# mux_side_A.net
KiCad netlist of a schematic drawn in Altium Designer
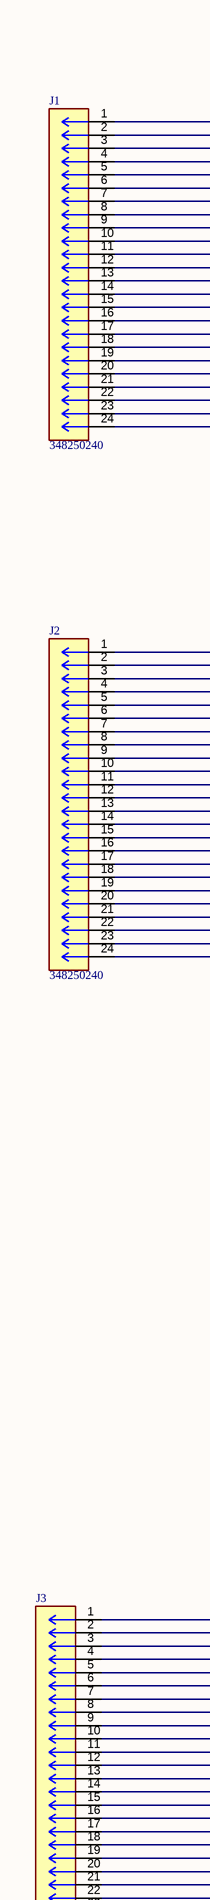
[diagram p0: mux side A (1-4).SchDoc, top left]
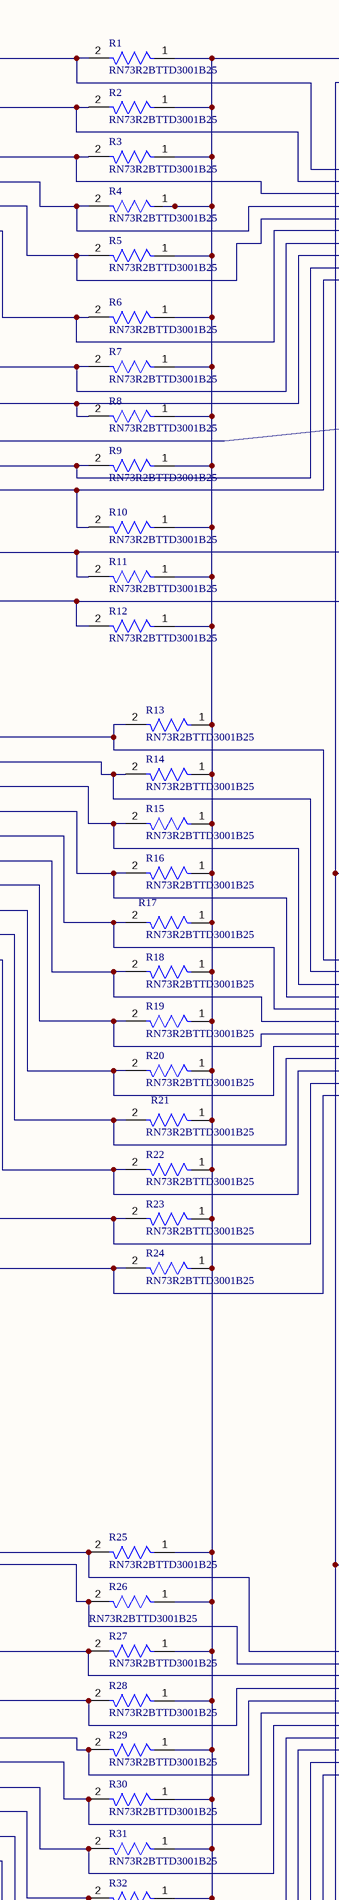
[diagram p1: mux side A (1-4).SchDoc, top middle]
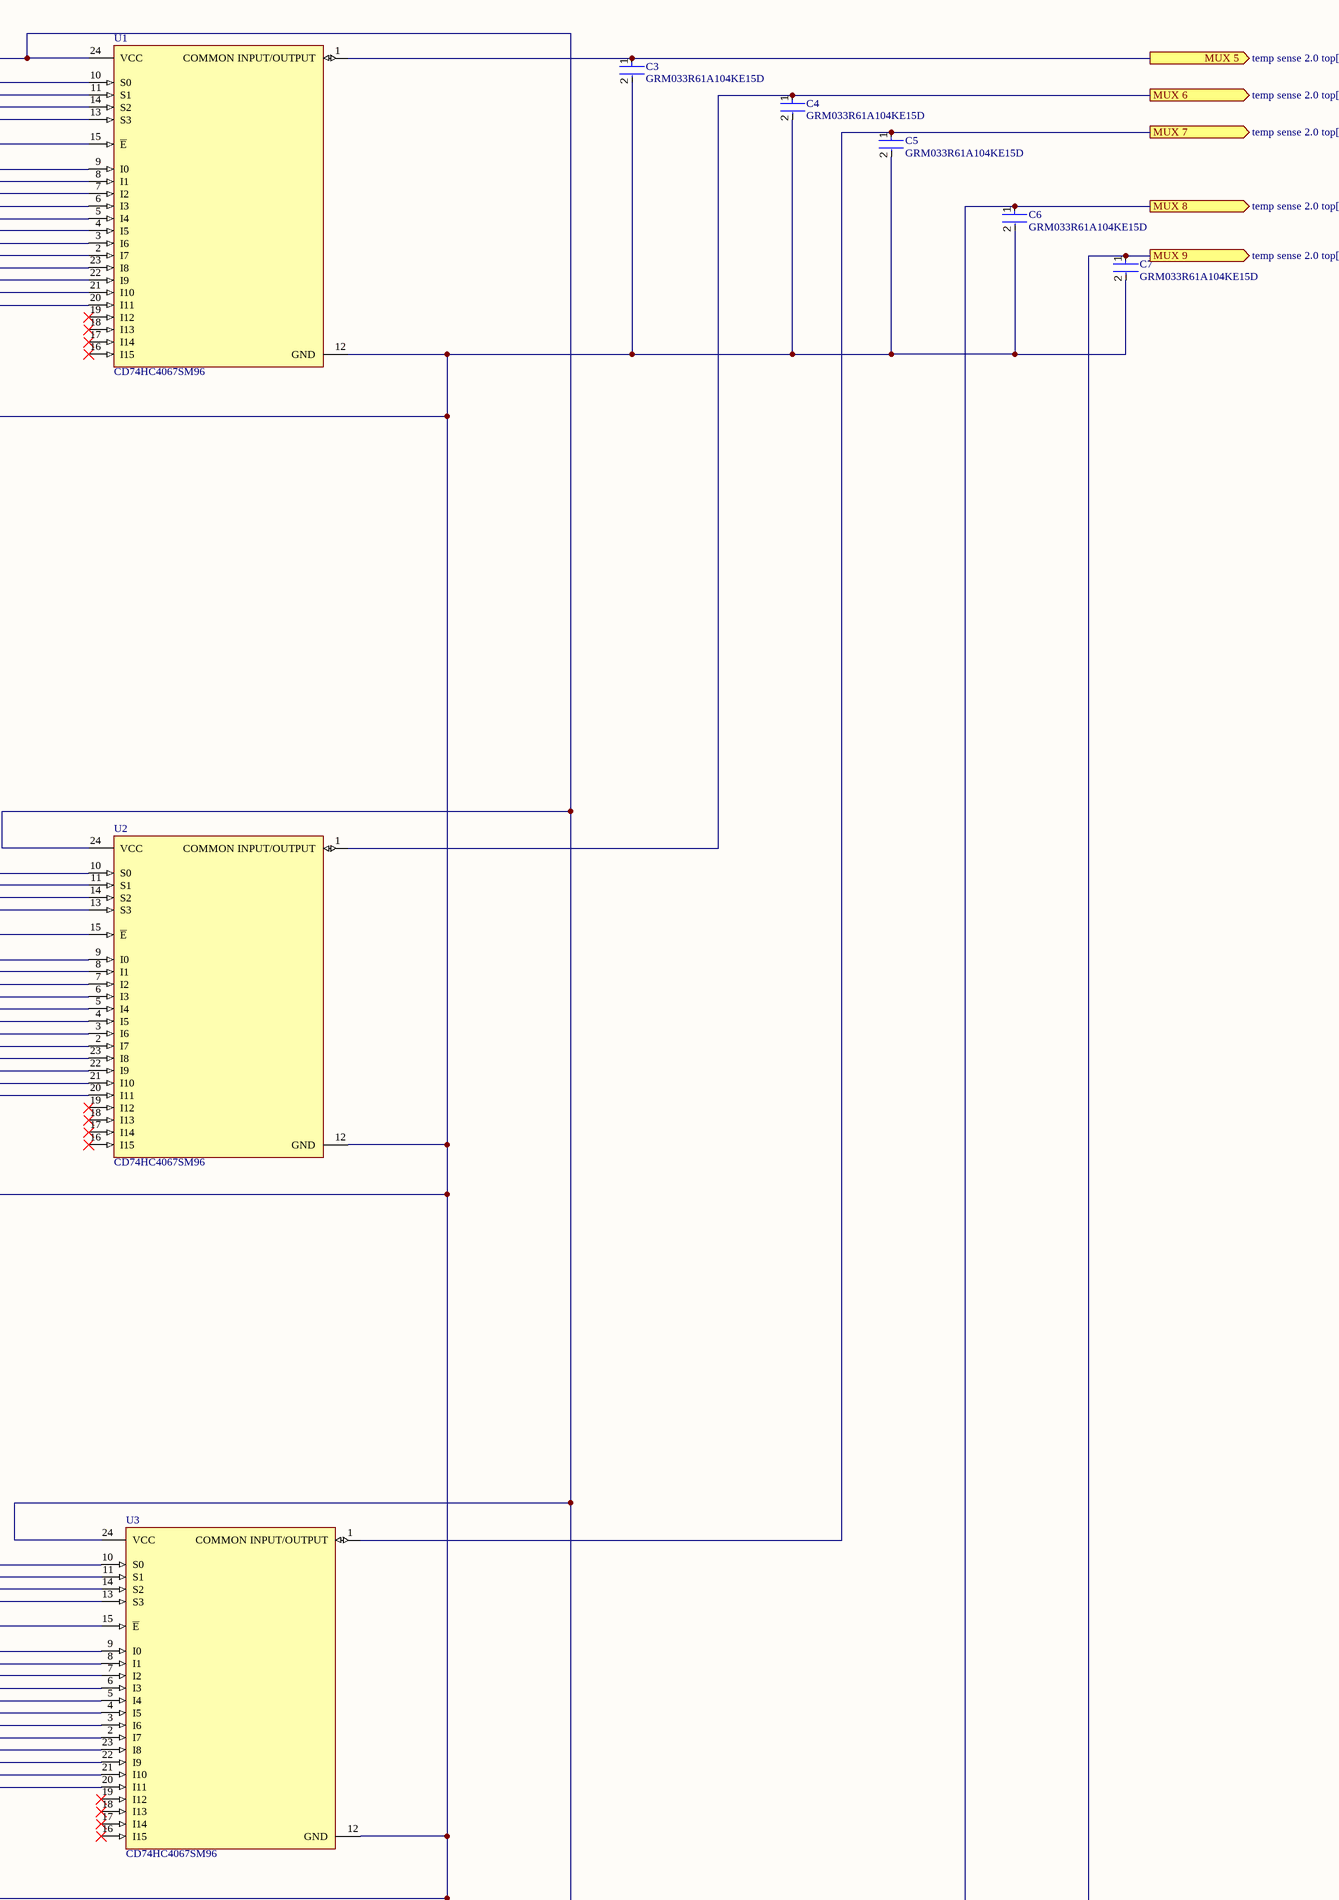
[diagram p2: mux side A (1-4).SchDoc, top right]
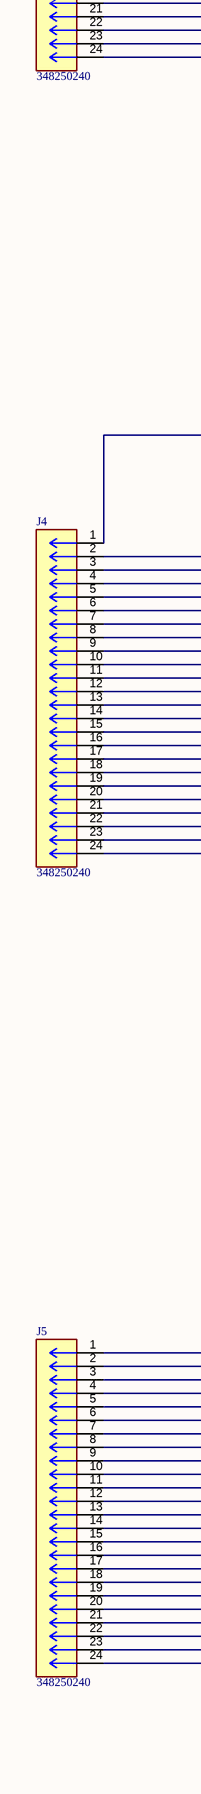
[diagram p3: mux side A (1-4).SchDoc, bottom left]
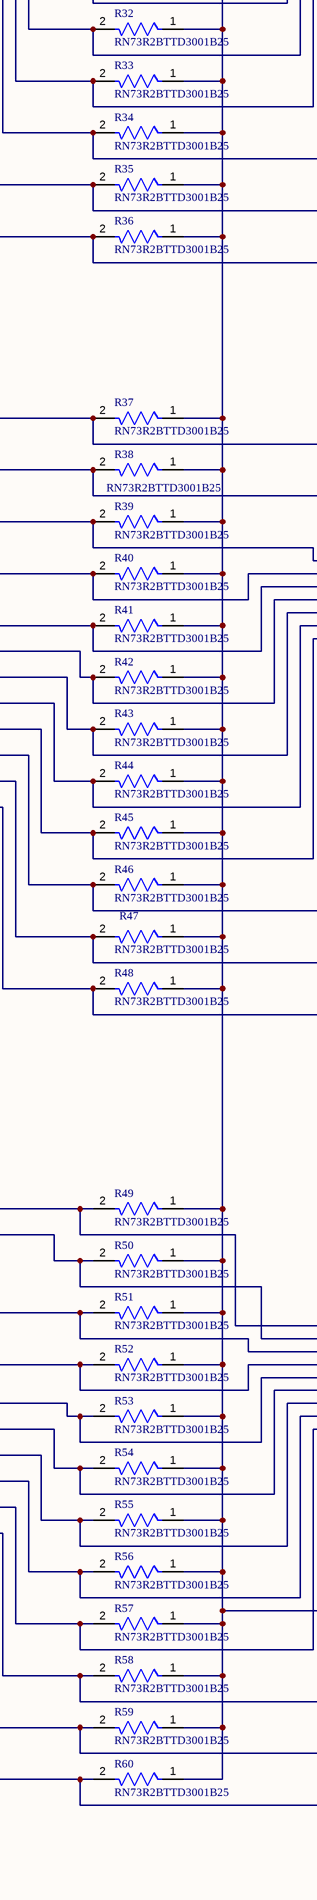
[diagram p4: mux side A (1-4).SchDoc, bottom middle]
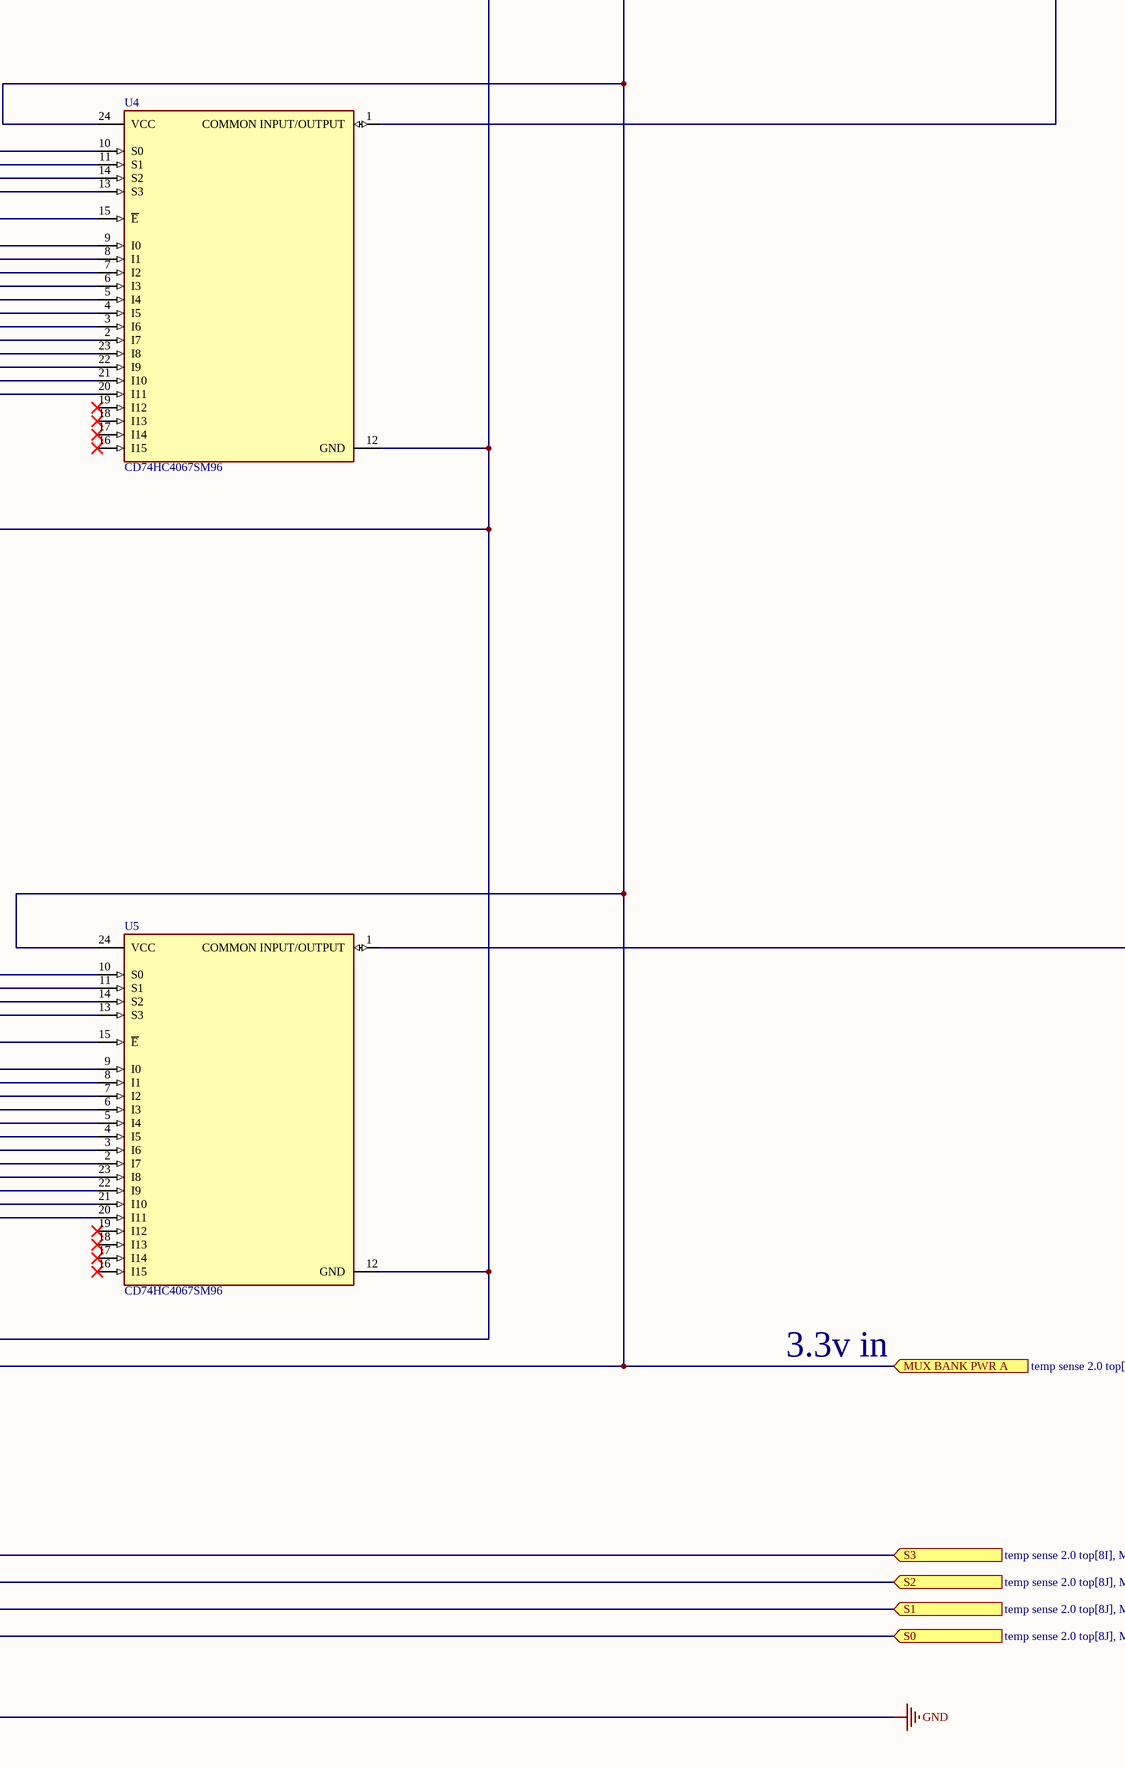
[diagram p5: mux side A (1-4).SchDoc, bottom right]

(export (version "E")
  (design (tool "Eeschema 10.0.6"))
  (components
    (comp (ref "C3")
      (value "GRM033R61A104KE15D")
      (footprint "FP-GRM033-0_03-IPC_C")
      (description "Chip Multilayer Ceramic Capacitors for General Purpose, 0201, 0.10uF, X5R, 15%, 10%, 10V")
      (fields (field (name "TOLERANCE") "10%") (field (name "VOLTAGE") "10V"))
      (libsource (lib "Altium Content Vault") (part "b4654b650e69147ec39a6b967a45e02"))
    )
    (comp (ref "C4")
      (value "GRM033R61A104KE15D")
      (footprint "FP-GRM033-0_03-IPC_C")
      (description "Chip Multilayer Ceramic Capacitors for General Purpose, 0201, 0.10uF, X5R, 15%, 10%, 10V")
      (fields (field (name "TOLERANCE") "10%") (field (name "VOLTAGE") "10V"))
      (libsource (lib "Altium Content Vault") (part "b4654b650e69147ec39a6b967a45e02"))
    )
    (comp (ref "C5")
      (value "GRM033R61A104KE15D")
      (footprint "FP-GRM033-0_03-IPC_C")
      (description "Chip Multilayer Ceramic Capacitors for General Purpose, 0201, 0.10uF, X5R, 15%, 10%, 10V")
      (fields (field (name "TOLERANCE") "10%") (field (name "VOLTAGE") "10V"))
      (libsource (lib "Altium Content Vault") (part "b4654b650e69147ec39a6b967a45e02"))
    )
    (comp (ref "C6")
      (value "GRM033R61A104KE15D")
      (footprint "FP-GRM033-0_03-IPC_C")
      (description "Chip Multilayer Ceramic Capacitors for General Purpose, 0201, 0.10uF, X5R, 15%, 10%, 10V")
      (fields (field (name "TOLERANCE") "10%") (field (name "VOLTAGE") "10V"))
      (libsource (lib "Altium Content Vault") (part "b4654b650e69147ec39a6b967a45e02"))
    )
    (comp (ref "C7")
      (value "GRM033R61A104KE15D")
      (footprint "FP-GRM033-0_03-IPC_C")
      (description "Chip Multilayer Ceramic Capacitors for General Purpose, 0201, 0.10uF, X5R, 15%, 10%, 10V")
      (fields (field (name "TOLERANCE") "10%") (field (name "VOLTAGE") "10V"))
      (libsource (lib "Altium Content Vault") (part "b4654b650e69147ec39a6b967a45e02"))
    )
    (comp (ref "J1")
      (value "348250240")
      (footprint "CONN_SD-34825-001_24_MOL")
      (libsource (lib "348250240") (part "348250240"))
    )
    (comp (ref "J2")
      (value "348250240")
      (footprint "CONN_SD-34825-001_24_MOL")
      (libsource (lib "348250240") (part "348250240"))
    )
    (comp (ref "J3")
      (value "348250240")
      (footprint "CONN_SD-34825-001_24_MOL")
      (libsource (lib "348250240") (part "348250240"))
    )
    (comp (ref "J4")
      (value "348250240")
      (footprint "CONN_SD-34825-001_24_MOL")
      (libsource (lib "348250240") (part "348250240"))
    )
    (comp (ref "J5")
      (value "348250240")
      (footprint "CONN_SD-34825-001_24_MOL")
      (libsource (lib "348250240") (part "348250240"))
    )
    (comp (ref "R1")
      (value "RN73R2BTTD3001B25")
      (footprint "FP-RN73R2B-IPC_A")
      (description "3kΩ ±0.1% 0.25W, 1/4W Chip Resistor 1206 (3216 Metric) Moisture Resistant Thin Film")
      (libsource (lib "Altium Content Vault") (part "1029c3af85768c4190bb7ad29bc67b5"))
    )
    (comp (ref "R2")
      (value "RN73R2BTTD3001B25")
      (footprint "FP-RN73R2B-IPC_A")
      (description "3kΩ ±0.1% 0.25W, 1/4W Chip Resistor 1206 (3216 Metric) Moisture Resistant Thin Film")
      (libsource (lib "Altium Content Vault") (part "1029c3af85768c4190bb7ad29bc67b5"))
    )
    (comp (ref "R3")
      (value "RN73R2BTTD3001B25")
      (footprint "FP-RN73R2B-IPC_A")
      (description "3kΩ ±0.1% 0.25W, 1/4W Chip Resistor 1206 (3216 Metric) Moisture Resistant Thin Film")
      (libsource (lib "Altium Content Vault") (part "1029c3af85768c4190bb7ad29bc67b5"))
    )
    (comp (ref "R4")
      (value "RN73R2BTTD3001B25")
      (footprint "FP-RN73R2B-IPC_A")
      (description "3kΩ ±0.1% 0.25W, 1/4W Chip Resistor 1206 (3216 Metric) Moisture Resistant Thin Film")
      (libsource (lib "Altium Content Vault") (part "1029c3af85768c4190bb7ad29bc67b5"))
    )
    (comp (ref "R5")
      (value "RN73R2BTTD3001B25")
      (footprint "FP-RN73R2B-IPC_A")
      (description "3kΩ ±0.1% 0.25W, 1/4W Chip Resistor 1206 (3216 Metric) Moisture Resistant Thin Film")
      (libsource (lib "Altium Content Vault") (part "1029c3af85768c4190bb7ad29bc67b5"))
    )
    (comp (ref "R6")
      (value "RN73R2BTTD3001B25")
      (footprint "FP-RN73R2B-IPC_A")
      (description "3kΩ ±0.1% 0.25W, 1/4W Chip Resistor 1206 (3216 Metric) Moisture Resistant Thin Film")
      (libsource (lib "Altium Content Vault") (part "1029c3af85768c4190bb7ad29bc67b5"))
    )
    (comp (ref "R7")
      (value "RN73R2BTTD3001B25")
      (footprint "FP-RN73R2B-IPC_A")
      (description "3kΩ ±0.1% 0.25W, 1/4W Chip Resistor 1206 (3216 Metric) Moisture Resistant Thin Film")
      (libsource (lib "Altium Content Vault") (part "1029c3af85768c4190bb7ad29bc67b5"))
    )
    (comp (ref "R8")
      (value "RN73R2BTTD3001B25")
      (footprint "FP-RN73R2B-IPC_A")
      (description "3kΩ ±0.1% 0.25W, 1/4W Chip Resistor 1206 (3216 Metric) Moisture Resistant Thin Film")
      (libsource (lib "Altium Content Vault") (part "1029c3af85768c4190bb7ad29bc67b5"))
    )
    (comp (ref "R9")
      (value "RN73R2BTTD3001B25")
      (footprint "FP-RN73R2B-IPC_A")
      (description "3kΩ ±0.1% 0.25W, 1/4W Chip Resistor 1206 (3216 Metric) Moisture Resistant Thin Film")
      (libsource (lib "Altium Content Vault") (part "1029c3af85768c4190bb7ad29bc67b5"))
    )
    (comp (ref "R10")
      (value "RN73R2BTTD3001B25")
      (footprint "FP-RN73R2B-IPC_A")
      (description "3kΩ ±0.1% 0.25W, 1/4W Chip Resistor 1206 (3216 Metric) Moisture Resistant Thin Film")
      (libsource (lib "Altium Content Vault") (part "1029c3af85768c4190bb7ad29bc67b5"))
    )
    (comp (ref "R11")
      (value "RN73R2BTTD3001B25")
      (footprint "FP-RN73R2B-IPC_A")
      (description "3kΩ ±0.1% 0.25W, 1/4W Chip Resistor 1206 (3216 Metric) Moisture Resistant Thin Film")
      (libsource (lib "Altium Content Vault") (part "1029c3af85768c4190bb7ad29bc67b5"))
    )
    (comp (ref "R12")
      (value "RN73R2BTTD3001B25")
      (footprint "FP-RN73R2B-IPC_A")
      (description "3kΩ ±0.1% 0.25W, 1/4W Chip Resistor 1206 (3216 Metric) Moisture Resistant Thin Film")
      (libsource (lib "Altium Content Vault") (part "1029c3af85768c4190bb7ad29bc67b5"))
    )
    (comp (ref "R13")
      (value "RN73R2BTTD3001B25")
      (footprint "FP-RN73R2B-IPC_A")
      (description "3kΩ ±0.1% 0.25W, 1/4W Chip Resistor 1206 (3216 Metric) Moisture Resistant Thin Film")
      (libsource (lib "Altium Content Vault") (part "1029c3af85768c4190bb7ad29bc67b5"))
    )
    (comp (ref "R14")
      (value "RN73R2BTTD3001B25")
      (footprint "FP-RN73R2B-IPC_A")
      (description "3kΩ ±0.1% 0.25W, 1/4W Chip Resistor 1206 (3216 Metric) Moisture Resistant Thin Film")
      (libsource (lib "Altium Content Vault") (part "1029c3af85768c4190bb7ad29bc67b5"))
    )
    (comp (ref "R15")
      (value "RN73R2BTTD3001B25")
      (footprint "FP-RN73R2B-IPC_A")
      (description "3kΩ ±0.1% 0.25W, 1/4W Chip Resistor 1206 (3216 Metric) Moisture Resistant Thin Film")
      (libsource (lib "Altium Content Vault") (part "1029c3af85768c4190bb7ad29bc67b5"))
    )
    (comp (ref "R16")
      (value "RN73R2BTTD3001B25")
      (footprint "FP-RN73R2B-IPC_A")
      (description "3kΩ ±0.1% 0.25W, 1/4W Chip Resistor 1206 (3216 Metric) Moisture Resistant Thin Film")
      (libsource (lib "Altium Content Vault") (part "1029c3af85768c4190bb7ad29bc67b5"))
    )
    (comp (ref "R17")
      (value "RN73R2BTTD3001B25")
      (footprint "FP-RN73R2B-IPC_A")
      (description "3kΩ ±0.1% 0.25W, 1/4W Chip Resistor 1206 (3216 Metric) Moisture Resistant Thin Film")
      (libsource (lib "Altium Content Vault") (part "1029c3af85768c4190bb7ad29bc67b5"))
    )
    (comp (ref "R18")
      (value "RN73R2BTTD3001B25")
      (footprint "FP-RN73R2B-IPC_A")
      (description "3kΩ ±0.1% 0.25W, 1/4W Chip Resistor 1206 (3216 Metric) Moisture Resistant Thin Film")
      (libsource (lib "Altium Content Vault") (part "1029c3af85768c4190bb7ad29bc67b5"))
    )
    (comp (ref "R19")
      (value "RN73R2BTTD3001B25")
      (footprint "FP-RN73R2B-IPC_A")
      (description "3kΩ ±0.1% 0.25W, 1/4W Chip Resistor 1206 (3216 Metric) Moisture Resistant Thin Film")
      (libsource (lib "Altium Content Vault") (part "1029c3af85768c4190bb7ad29bc67b5"))
    )
    (comp (ref "R20")
      (value "RN73R2BTTD3001B25")
      (footprint "FP-RN73R2B-IPC_A")
      (description "3kΩ ±0.1% 0.25W, 1/4W Chip Resistor 1206 (3216 Metric) Moisture Resistant Thin Film")
      (libsource (lib "Altium Content Vault") (part "1029c3af85768c4190bb7ad29bc67b5"))
    )
    (comp (ref "R21")
      (value "RN73R2BTTD3001B25")
      (footprint "FP-RN73R2B-IPC_A")
      (description "3kΩ ±0.1% 0.25W, 1/4W Chip Resistor 1206 (3216 Metric) Moisture Resistant Thin Film")
      (libsource (lib "Altium Content Vault") (part "1029c3af85768c4190bb7ad29bc67b5"))
    )
    (comp (ref "R22")
      (value "RN73R2BTTD3001B25")
      (footprint "FP-RN73R2B-IPC_A")
      (description "3kΩ ±0.1% 0.25W, 1/4W Chip Resistor 1206 (3216 Metric) Moisture Resistant Thin Film")
      (libsource (lib "Altium Content Vault") (part "1029c3af85768c4190bb7ad29bc67b5"))
    )
    (comp (ref "R23")
      (value "RN73R2BTTD3001B25")
      (footprint "FP-RN73R2B-IPC_A")
      (description "3kΩ ±0.1% 0.25W, 1/4W Chip Resistor 1206 (3216 Metric) Moisture Resistant Thin Film")
      (libsource (lib "Altium Content Vault") (part "1029c3af85768c4190bb7ad29bc67b5"))
    )
    (comp (ref "R24")
      (value "RN73R2BTTD3001B25")
      (footprint "FP-RN73R2B-IPC_A")
      (description "3kΩ ±0.1% 0.25W, 1/4W Chip Resistor 1206 (3216 Metric) Moisture Resistant Thin Film")
      (libsource (lib "Altium Content Vault") (part "1029c3af85768c4190bb7ad29bc67b5"))
    )
    (comp (ref "R25")
      (value "RN73R2BTTD3001B25")
      (footprint "FP-RN73R2B-IPC_A")
      (description "3kΩ ±0.1% 0.25W, 1/4W Chip Resistor 1206 (3216 Metric) Moisture Resistant Thin Film")
      (libsource (lib "Altium Content Vault") (part "1029c3af85768c4190bb7ad29bc67b5"))
    )
    (comp (ref "R26")
      (value "RN73R2BTTD3001B25")
      (footprint "FP-RN73R2B-IPC_A")
      (description "3kΩ ±0.1% 0.25W, 1/4W Chip Resistor 1206 (3216 Metric) Moisture Resistant Thin Film")
      (libsource (lib "Altium Content Vault") (part "1029c3af85768c4190bb7ad29bc67b5"))
    )
    (comp (ref "R27")
      (value "RN73R2BTTD3001B25")
      (footprint "FP-RN73R2B-IPC_A")
      (description "3kΩ ±0.1% 0.25W, 1/4W Chip Resistor 1206 (3216 Metric) Moisture Resistant Thin Film")
      (libsource (lib "Altium Content Vault") (part "1029c3af85768c4190bb7ad29bc67b5"))
    )
    (comp (ref "R28")
      (value "RN73R2BTTD3001B25")
      (footprint "FP-RN73R2B-IPC_A")
      (description "3kΩ ±0.1% 0.25W, 1/4W Chip Resistor 1206 (3216 Metric) Moisture Resistant Thin Film")
      (libsource (lib "Altium Content Vault") (part "1029c3af85768c4190bb7ad29bc67b5"))
    )
    (comp (ref "R29")
      (value "RN73R2BTTD3001B25")
      (footprint "FP-RN73R2B-IPC_A")
      (description "3kΩ ±0.1% 0.25W, 1/4W Chip Resistor 1206 (3216 Metric) Moisture Resistant Thin Film")
      (libsource (lib "Altium Content Vault") (part "1029c3af85768c4190bb7ad29bc67b5"))
    )
    (comp (ref "R30")
      (value "RN73R2BTTD3001B25")
      (footprint "FP-RN73R2B-IPC_A")
      (description "3kΩ ±0.1% 0.25W, 1/4W Chip Resistor 1206 (3216 Metric) Moisture Resistant Thin Film")
      (libsource (lib "Altium Content Vault") (part "1029c3af85768c4190bb7ad29bc67b5"))
    )
    (comp (ref "R31")
      (value "RN73R2BTTD3001B25")
      (footprint "FP-RN73R2B-IPC_A")
      (description "3kΩ ±0.1% 0.25W, 1/4W Chip Resistor 1206 (3216 Metric) Moisture Resistant Thin Film")
      (libsource (lib "Altium Content Vault") (part "1029c3af85768c4190bb7ad29bc67b5"))
    )
    (comp (ref "R32")
      (value "RN73R2BTTD3001B25")
      (footprint "FP-RN73R2B-IPC_A")
      (description "3kΩ ±0.1% 0.25W, 1/4W Chip Resistor 1206 (3216 Metric) Moisture Resistant Thin Film")
      (libsource (lib "Altium Content Vault") (part "1029c3af85768c4190bb7ad29bc67b5"))
    )
    (comp (ref "R33")
      (value "RN73R2BTTD3001B25")
      (footprint "FP-RN73R2B-IPC_A")
      (description "3kΩ ±0.1% 0.25W, 1/4W Chip Resistor 1206 (3216 Metric) Moisture Resistant Thin Film")
      (libsource (lib "Altium Content Vault") (part "1029c3af85768c4190bb7ad29bc67b5"))
    )
    (comp (ref "R34")
      (value "RN73R2BTTD3001B25")
      (footprint "FP-RN73R2B-IPC_A")
      (description "3kΩ ±0.1% 0.25W, 1/4W Chip Resistor 1206 (3216 Metric) Moisture Resistant Thin Film")
      (libsource (lib "Altium Content Vault") (part "1029c3af85768c4190bb7ad29bc67b5"))
    )
    (comp (ref "R35")
      (value "RN73R2BTTD3001B25")
      (footprint "FP-RN73R2B-IPC_A")
      (description "3kΩ ±0.1% 0.25W, 1/4W Chip Resistor 1206 (3216 Metric) Moisture Resistant Thin Film")
      (libsource (lib "Altium Content Vault") (part "1029c3af85768c4190bb7ad29bc67b5"))
    )
    (comp (ref "R36")
      (value "RN73R2BTTD3001B25")
      (footprint "FP-RN73R2B-IPC_A")
      (description "3kΩ ±0.1% 0.25W, 1/4W Chip Resistor 1206 (3216 Metric) Moisture Resistant Thin Film")
      (libsource (lib "Altium Content Vault") (part "1029c3af85768c4190bb7ad29bc67b5"))
    )
    (comp (ref "R37")
      (value "RN73R2BTTD3001B25")
      (footprint "FP-RN73R2B-IPC_A")
      (description "3kΩ ±0.1% 0.25W, 1/4W Chip Resistor 1206 (3216 Metric) Moisture Resistant Thin Film")
      (libsource (lib "Altium Content Vault") (part "1029c3af85768c4190bb7ad29bc67b5"))
    )
    (comp (ref "R38")
      (value "RN73R2BTTD3001B25")
      (footprint "FP-RN73R2B-IPC_A")
      (description "3kΩ ±0.1% 0.25W, 1/4W Chip Resistor 1206 (3216 Metric) Moisture Resistant Thin Film")
      (libsource (lib "Altium Content Vault") (part "1029c3af85768c4190bb7ad29bc67b5"))
    )
    (comp (ref "R39")
      (value "RN73R2BTTD3001B25")
      (footprint "FP-RN73R2B-IPC_A")
      (description "3kΩ ±0.1% 0.25W, 1/4W Chip Resistor 1206 (3216 Metric) Moisture Resistant Thin Film")
      (libsource (lib "Altium Content Vault") (part "1029c3af85768c4190bb7ad29bc67b5"))
    )
    (comp (ref "R40")
      (value "RN73R2BTTD3001B25")
      (footprint "FP-RN73R2B-IPC_A")
      (description "3kΩ ±0.1% 0.25W, 1/4W Chip Resistor 1206 (3216 Metric) Moisture Resistant Thin Film")
      (libsource (lib "Altium Content Vault") (part "1029c3af85768c4190bb7ad29bc67b5"))
    )
    (comp (ref "R41")
      (value "RN73R2BTTD3001B25")
      (footprint "FP-RN73R2B-IPC_A")
      (description "3kΩ ±0.1% 0.25W, 1/4W Chip Resistor 1206 (3216 Metric) Moisture Resistant Thin Film")
      (libsource (lib "Altium Content Vault") (part "1029c3af85768c4190bb7ad29bc67b5"))
    )
    (comp (ref "R42")
      (value "RN73R2BTTD3001B25")
      (footprint "FP-RN73R2B-IPC_A")
      (description "3kΩ ±0.1% 0.25W, 1/4W Chip Resistor 1206 (3216 Metric) Moisture Resistant Thin Film")
      (libsource (lib "Altium Content Vault") (part "1029c3af85768c4190bb7ad29bc67b5"))
    )
    (comp (ref "R43")
      (value "RN73R2BTTD3001B25")
      (footprint "FP-RN73R2B-IPC_A")
      (description "3kΩ ±0.1% 0.25W, 1/4W Chip Resistor 1206 (3216 Metric) Moisture Resistant Thin Film")
      (libsource (lib "Altium Content Vault") (part "1029c3af85768c4190bb7ad29bc67b5"))
    )
    (comp (ref "R44")
      (value "RN73R2BTTD3001B25")
      (footprint "FP-RN73R2B-IPC_A")
      (description "3kΩ ±0.1% 0.25W, 1/4W Chip Resistor 1206 (3216 Metric) Moisture Resistant Thin Film")
      (libsource (lib "Altium Content Vault") (part "1029c3af85768c4190bb7ad29bc67b5"))
    )
    (comp (ref "R45")
      (value "RN73R2BTTD3001B25")
      (footprint "FP-RN73R2B-IPC_A")
      (description "3kΩ ±0.1% 0.25W, 1/4W Chip Resistor 1206 (3216 Metric) Moisture Resistant Thin Film")
      (libsource (lib "Altium Content Vault") (part "1029c3af85768c4190bb7ad29bc67b5"))
    )
    (comp (ref "R46")
      (value "RN73R2BTTD3001B25")
      (footprint "FP-RN73R2B-IPC_A")
      (description "3kΩ ±0.1% 0.25W, 1/4W Chip Resistor 1206 (3216 Metric) Moisture Resistant Thin Film")
      (libsource (lib "Altium Content Vault") (part "1029c3af85768c4190bb7ad29bc67b5"))
    )
    (comp (ref "R47")
      (value "RN73R2BTTD3001B25")
      (footprint "FP-RN73R2B-IPC_A")
      (description "3kΩ ±0.1% 0.25W, 1/4W Chip Resistor 1206 (3216 Metric) Moisture Resistant Thin Film")
      (libsource (lib "Altium Content Vault") (part "1029c3af85768c4190bb7ad29bc67b5"))
    )
    (comp (ref "R48")
      (value "RN73R2BTTD3001B25")
      (footprint "FP-RN73R2B-IPC_A")
      (description "3kΩ ±0.1% 0.25W, 1/4W Chip Resistor 1206 (3216 Metric) Moisture Resistant Thin Film")
      (libsource (lib "Altium Content Vault") (part "1029c3af85768c4190bb7ad29bc67b5"))
    )
    (comp (ref "R49")
      (value "RN73R2BTTD3001B25")
      (footprint "FP-RN73R2B-IPC_A")
      (description "3kΩ ±0.1% 0.25W, 1/4W Chip Resistor 1206 (3216 Metric) Moisture Resistant Thin Film")
      (libsource (lib "Altium Content Vault") (part "1029c3af85768c4190bb7ad29bc67b5"))
    )
    (comp (ref "R50")
      (value "RN73R2BTTD3001B25")
      (footprint "FP-RN73R2B-IPC_A")
      (description "3kΩ ±0.1% 0.25W, 1/4W Chip Resistor 1206 (3216 Metric) Moisture Resistant Thin Film")
      (libsource (lib "Altium Content Vault") (part "1029c3af85768c4190bb7ad29bc67b5"))
    )
    (comp (ref "R51")
      (value "RN73R2BTTD3001B25")
      (footprint "FP-RN73R2B-IPC_A")
      (description "3kΩ ±0.1% 0.25W, 1/4W Chip Resistor 1206 (3216 Metric) Moisture Resistant Thin Film")
      (libsource (lib "Altium Content Vault") (part "1029c3af85768c4190bb7ad29bc67b5"))
    )
    (comp (ref "R52")
      (value "RN73R2BTTD3001B25")
      (footprint "FP-RN73R2B-IPC_A")
      (description "3kΩ ±0.1% 0.25W, 1/4W Chip Resistor 1206 (3216 Metric) Moisture Resistant Thin Film")
      (libsource (lib "Altium Content Vault") (part "1029c3af85768c4190bb7ad29bc67b5"))
    )
    (comp (ref "R53")
      (value "RN73R2BTTD3001B25")
      (footprint "FP-RN73R2B-IPC_A")
      (description "3kΩ ±0.1% 0.25W, 1/4W Chip Resistor 1206 (3216 Metric) Moisture Resistant Thin Film")
      (libsource (lib "Altium Content Vault") (part "1029c3af85768c4190bb7ad29bc67b5"))
    )
    (comp (ref "R54")
      (value "RN73R2BTTD3001B25")
      (footprint "FP-RN73R2B-IPC_A")
      (description "3kΩ ±0.1% 0.25W, 1/4W Chip Resistor 1206 (3216 Metric) Moisture Resistant Thin Film")
      (libsource (lib "Altium Content Vault") (part "1029c3af85768c4190bb7ad29bc67b5"))
    )
    (comp (ref "R55")
      (value "RN73R2BTTD3001B25")
      (footprint "FP-RN73R2B-IPC_A")
      (description "3kΩ ±0.1% 0.25W, 1/4W Chip Resistor 1206 (3216 Metric) Moisture Resistant Thin Film")
      (libsource (lib "Altium Content Vault") (part "1029c3af85768c4190bb7ad29bc67b5"))
    )
    (comp (ref "R56")
      (value "RN73R2BTTD3001B25")
      (footprint "FP-RN73R2B-IPC_A")
      (description "3kΩ ±0.1% 0.25W, 1/4W Chip Resistor 1206 (3216 Metric) Moisture Resistant Thin Film")
      (libsource (lib "Altium Content Vault") (part "1029c3af85768c4190bb7ad29bc67b5"))
    )
    (comp (ref "R57")
      (value "RN73R2BTTD3001B25")
      (footprint "FP-RN73R2B-IPC_A")
      (description "3kΩ ±0.1% 0.25W, 1/4W Chip Resistor 1206 (3216 Metric) Moisture Resistant Thin Film")
      (libsource (lib "Altium Content Vault") (part "1029c3af85768c4190bb7ad29bc67b5"))
    )
    (comp (ref "R58")
      (value "RN73R2BTTD3001B25")
      (footprint "FP-RN73R2B-IPC_A")
      (description "3kΩ ±0.1% 0.25W, 1/4W Chip Resistor 1206 (3216 Metric) Moisture Resistant Thin Film")
      (libsource (lib "Altium Content Vault") (part "1029c3af85768c4190bb7ad29bc67b5"))
    )
    (comp (ref "R59")
      (value "RN73R2BTTD3001B25")
      (footprint "FP-RN73R2B-IPC_A")
      (description "3kΩ ±0.1% 0.25W, 1/4W Chip Resistor 1206 (3216 Metric) Moisture Resistant Thin Film")
      (libsource (lib "Altium Content Vault") (part "1029c3af85768c4190bb7ad29bc67b5"))
    )
    (comp (ref "R60")
      (value "RN73R2BTTD3001B25")
      (footprint "FP-RN73R2B-IPC_A")
      (description "3kΩ ±0.1% 0.25W, 1/4W Chip Resistor 1206 (3216 Metric) Moisture Resistant Thin Film")
      (libsource (lib "Altium Content Vault") (part "1029c3af85768c4190bb7ad29bc67b5"))
    )
    (comp (ref "U1")
      (value "CD74HC4067SM96")
      (footprint "FP-DB0024A-IPC_C")
      (description "IC MUX/DEMUX 1X16 24SSOP")
      (libsource (lib "Altium Content Vault") (part "3c03c7c8a240a5fb11098c607706683"))
    )
    (comp (ref "U2")
      (value "CD74HC4067SM96")
      (footprint "FP-DB0024A-IPC_C")
      (description "IC MUX/DEMUX 1X16 24SSOP")
      (libsource (lib "Altium Content Vault") (part "3c03c7c8a240a5fb11098c607706683"))
    )
    (comp (ref "U3")
      (value "CD74HC4067SM96")
      (footprint "FP-DB0024A-IPC_C")
      (description "IC MUX/DEMUX 1X16 24SSOP")
      (libsource (lib "Altium Content Vault") (part "3c03c7c8a240a5fb11098c607706683"))
    )
    (comp (ref "U4")
      (value "CD74HC4067SM96")
      (footprint "FP-DB0024A-IPC_C")
      (description "IC MUX/DEMUX 1X16 24SSOP")
      (libsource (lib "Altium Content Vault") (part "3c03c7c8a240a5fb11098c607706683"))
    )
    (comp (ref "U5")
      (value "CD74HC4067SM96")
      (footprint "FP-DB0024A-IPC_C")
      (description "IC MUX/DEMUX 1X16 24SSOP")
      (libsource (lib "Altium Content Vault") (part "3c03c7c8a240a5fb11098c607706683"))
    )
  )
  (nets
    (net (code "1") (name "/MUX 5") (class "Default")
      (node (ref "C3") (pin "1") (pinfunction "1_1") (pintype "passive"))
      (node (ref "U1") (pin "1") (pinfunction "COMMON_INPUT/OUTPUT_1") (pintype "bidirectional"))
    )
    (net (code "2") (name "/MUX 6") (class "Default")
      (node (ref "C4") (pin "1") (pinfunction "1_1") (pintype "passive"))
      (node (ref "U2") (pin "1") (pinfunction "COMMON_INPUT/OUTPUT_1") (pintype "bidirectional"))
    )
    (net (code "3") (name "/MUX 7") (class "Default")
      (node (ref "C5") (pin "1") (pinfunction "1_1") (pintype "passive"))
      (node (ref "U3") (pin "1") (pinfunction "COMMON_INPUT/OUTPUT_1") (pintype "bidirectional"))
    )
    (net (code "4") (name "/MUX 8") (class "Default")
      (node (ref "C6") (pin "1") (pinfunction "1_1") (pintype "passive"))
      (node (ref "U4") (pin "1") (pinfunction "COMMON_INPUT/OUTPUT_1") (pintype "bidirectional"))
    )
    (net (code "5") (name "/MUX 9") (class "Default")
      (node (ref "C7") (pin "1") (pinfunction "1_1") (pintype "passive"))
      (node (ref "U5") (pin "1") (pinfunction "COMMON_INPUT/OUTPUT_1") (pintype "bidirectional"))
    )
    (net (code "6") (name "/MUX BANK PWR A") (class "Default")
      (node (ref "R1") (pin "1") (pinfunction "1_1") (pintype "passive"))
      (node (ref "R10") (pin "1") (pinfunction "1_1") (pintype "passive"))
      (node (ref "R11") (pin "1") (pinfunction "1_1") (pintype "passive"))
      (node (ref "R12") (pin "1") (pinfunction "1_1") (pintype "passive"))
      (node (ref "R13") (pin "1") (pinfunction "1_1") (pintype "passive"))
      (node (ref "R14") (pin "1") (pinfunction "1_1") (pintype "passive"))
      (node (ref "R15") (pin "1") (pinfunction "1_1") (pintype "passive"))
      (node (ref "R16") (pin "1") (pinfunction "1_1") (pintype "passive"))
      (node (ref "R17") (pin "1") (pinfunction "1_1") (pintype "passive"))
      (node (ref "R18") (pin "1") (pinfunction "1_1") (pintype "passive"))
      (node (ref "R19") (pin "1") (pinfunction "1_1") (pintype "passive"))
      (node (ref "R2") (pin "1") (pinfunction "1_1") (pintype "passive"))
      (node (ref "R20") (pin "1") (pinfunction "1_1") (pintype "passive"))
      (node (ref "R21") (pin "1") (pinfunction "1_1") (pintype "passive"))
      (node (ref "R22") (pin "1") (pinfunction "1_1") (pintype "passive"))
      (node (ref "R23") (pin "1") (pinfunction "1_1") (pintype "passive"))
      (node (ref "R24") (pin "1") (pinfunction "1_1") (pintype "passive"))
      (node (ref "R25") (pin "1") (pinfunction "1_1") (pintype "passive"))
      (node (ref "R26") (pin "1") (pinfunction "1_1") (pintype "passive"))
      (node (ref "R27") (pin "1") (pinfunction "1_1") (pintype "passive"))
      (node (ref "R28") (pin "1") (pinfunction "1_1") (pintype "passive"))
      (node (ref "R29") (pin "1") (pinfunction "1_1") (pintype "passive"))
      (node (ref "R3") (pin "1") (pinfunction "1_1") (pintype "passive"))
      (node (ref "R30") (pin "1") (pinfunction "1_1") (pintype "passive"))
      (node (ref "R31") (pin "1") (pinfunction "1_1") (pintype "passive"))
      (node (ref "R32") (pin "1") (pinfunction "1_1") (pintype "passive"))
      (node (ref "R33") (pin "1") (pinfunction "1_1") (pintype "passive"))
      (node (ref "R34") (pin "1") (pinfunction "1_1") (pintype "passive"))
      (node (ref "R35") (pin "1") (pinfunction "1_1") (pintype "passive"))
      (node (ref "R36") (pin "1") (pinfunction "1_1") (pintype "passive"))
      (node (ref "R37") (pin "1") (pinfunction "1_1") (pintype "passive"))
      (node (ref "R38") (pin "1") (pinfunction "1_1") (pintype "passive"))
      (node (ref "R39") (pin "1") (pinfunction "1_1") (pintype "passive"))
      (node (ref "R4") (pin "1") (pinfunction "1_1") (pintype "passive"))
      (node (ref "R40") (pin "1") (pinfunction "1_1") (pintype "passive"))
      (node (ref "R41") (pin "1") (pinfunction "1_1") (pintype "passive"))
      (node (ref "R42") (pin "1") (pinfunction "1_1") (pintype "passive"))
      (node (ref "R43") (pin "1") (pinfunction "1_1") (pintype "passive"))
      (node (ref "R44") (pin "1") (pinfunction "1_1") (pintype "passive"))
      (node (ref "R45") (pin "1") (pinfunction "1_1") (pintype "passive"))
      (node (ref "R46") (pin "1") (pinfunction "1_1") (pintype "passive"))
      (node (ref "R47") (pin "1") (pinfunction "1_1") (pintype "passive"))
      (node (ref "R48") (pin "1") (pinfunction "1_1") (pintype "passive"))
      (node (ref "R49") (pin "1") (pinfunction "1_1") (pintype "passive"))
      (node (ref "R5") (pin "1") (pinfunction "1_1") (pintype "passive"))
      (node (ref "R50") (pin "1") (pinfunction "1_1") (pintype "passive"))
      (node (ref "R51") (pin "1") (pinfunction "1_1") (pintype "passive"))
      (node (ref "R52") (pin "1") (pinfunction "1_1") (pintype "passive"))
      (node (ref "R53") (pin "1") (pinfunction "1_1") (pintype "passive"))
      (node (ref "R54") (pin "1") (pinfunction "1_1") (pintype "passive"))
      (node (ref "R55") (pin "1") (pinfunction "1_1") (pintype "passive"))
      (node (ref "R56") (pin "1") (pinfunction "1_1") (pintype "passive"))
      (node (ref "R57") (pin "1") (pinfunction "1_1") (pintype "passive"))
      (node (ref "R58") (pin "1") (pinfunction "1_1") (pintype "passive"))
      (node (ref "R59") (pin "1") (pinfunction "1_1") (pintype "passive"))
      (node (ref "R6") (pin "1") (pinfunction "1_1") (pintype "passive"))
      (node (ref "R60") (pin "1") (pinfunction "1_1") (pintype "passive"))
      (node (ref "R7") (pin "1") (pinfunction "1_1") (pintype "passive"))
      (node (ref "R8") (pin "1") (pinfunction "1_1") (pintype "passive"))
      (node (ref "R9") (pin "1") (pinfunction "1_1") (pintype "passive"))
      (node (ref "U1") (pin "24") (pinfunction "VCC_24") (pintype "power_in"))
      (node (ref "U2") (pin "24") (pinfunction "VCC_24") (pintype "power_in"))
      (node (ref "U3") (pin "24") (pinfunction "VCC_24") (pintype "power_in"))
      (node (ref "U4") (pin "24") (pinfunction "VCC_24") (pintype "power_in"))
      (node (ref "U5") (pin "24") (pinfunction "VCC_24") (pintype "power_in"))
    )
    (net (code "7") (name "/S0") (class "Default")
      (node (ref "U1") (pin "10") (pinfunction "S0_10") (pintype "input"))
      (node (ref "U2") (pin "10") (pinfunction "S0_10") (pintype "input"))
      (node (ref "U3") (pin "10") (pinfunction "S0_10") (pintype "input"))
      (node (ref "U4") (pin "10") (pinfunction "S0_10") (pintype "input"))
      (node (ref "U5") (pin "10") (pinfunction "S0_10") (pintype "input"))
    )
    (net (code "8") (name "/S1") (class "Default")
      (node (ref "U1") (pin "11") (pinfunction "S1_11") (pintype "input"))
      (node (ref "U2") (pin "11") (pinfunction "S1_11") (pintype "input"))
      (node (ref "U3") (pin "11") (pinfunction "S1_11") (pintype "input"))
      (node (ref "U4") (pin "11") (pinfunction "S1_11") (pintype "input"))
      (node (ref "U5") (pin "11") (pinfunction "S1_11") (pintype "input"))
    )
    (net (code "9") (name "/S2") (class "Default")
      (node (ref "U1") (pin "14") (pinfunction "S2_14") (pintype "input"))
      (node (ref "U2") (pin "14") (pinfunction "S2_14") (pintype "input"))
      (node (ref "U3") (pin "14") (pinfunction "S2_14") (pintype "input"))
      (node (ref "U4") (pin "14") (pinfunction "S2_14") (pintype "input"))
      (node (ref "U5") (pin "14") (pinfunction "S2_14") (pintype "input"))
    )
    (net (code "10") (name "/S3") (class "Default")
      (node (ref "U1") (pin "13") (pinfunction "S3_13") (pintype "input"))
      (node (ref "U2") (pin "13") (pinfunction "S3_13") (pintype "input"))
      (node (ref "U3") (pin "13") (pinfunction "S3_13") (pintype "input"))
      (node (ref "U4") (pin "13") (pinfunction "S3_13") (pintype "input"))
      (node (ref "U5") (pin "13") (pinfunction "S3_13") (pintype "input"))
    )
    (net (code "11") (name "GND") (class "Default")
      (node (ref "C3") (pin "2") (pinfunction "2_2") (pintype "passive"))
      (node (ref "C4") (pin "2") (pinfunction "2_2") (pintype "passive"))
      (node (ref "C5") (pin "2") (pinfunction "2_2") (pintype "passive"))
      (node (ref "C6") (pin "2") (pinfunction "2_2") (pintype "passive"))
      (node (ref "C7") (pin "2") (pinfunction "2_2") (pintype "passive"))
      (node (ref "J1") (pin "10") (pinfunction "10_10") (pintype "passive"))
      (node (ref "J1") (pin "12") (pinfunction "12_12") (pintype "passive"))
      (node (ref "J1") (pin "14") (pinfunction "14_14") (pintype "passive"))
      (node (ref "J1") (pin "16") (pinfunction "16_16") (pintype "passive"))
      (node (ref "J1") (pin "18") (pinfunction "18_18") (pintype "passive"))
      (node (ref "J1") (pin "2") (pinfunction "2_2") (pintype "passive"))
      (node (ref "J1") (pin "20") (pinfunction "20_20") (pintype "passive"))
      (node (ref "J1") (pin "22") (pinfunction "22_22") (pintype "passive"))
      (node (ref "J1") (pin "24") (pinfunction "24_24") (pintype "passive"))
      (node (ref "J1") (pin "4") (pinfunction "4_4") (pintype "passive"))
      (node (ref "J1") (pin "6") (pinfunction "6_6") (pintype "passive"))
      (node (ref "J1") (pin "8") (pinfunction "8_8") (pintype "passive"))
      (node (ref "J2") (pin "10") (pinfunction "10_10") (pintype "passive"))
      (node (ref "J2") (pin "12") (pinfunction "12_12") (pintype "passive"))
      (node (ref "J2") (pin "14") (pinfunction "14_14") (pintype "passive"))
      (node (ref "J2") (pin "16") (pinfunction "16_16") (pintype "passive"))
      (node (ref "J2") (pin "18") (pinfunction "18_18") (pintype "passive"))
      (node (ref "J2") (pin "2") (pinfunction "2_2") (pintype "passive"))
      (node (ref "J2") (pin "20") (pinfunction "20_20") (pintype "passive"))
      (node (ref "J2") (pin "22") (pinfunction "22_22") (pintype "passive"))
      (node (ref "J2") (pin "24") (pinfunction "24_24") (pintype "passive"))
      (node (ref "J2") (pin "4") (pinfunction "4_4") (pintype "passive"))
      (node (ref "J2") (pin "6") (pinfunction "6_6") (pintype "passive"))
      (node (ref "J2") (pin "8") (pinfunction "8_8") (pintype "passive"))
      (node (ref "J3") (pin "10") (pinfunction "10_10") (pintype "passive"))
      (node (ref "J3") (pin "12") (pinfunction "12_12") (pintype "passive"))
      (node (ref "J3") (pin "14") (pinfunction "14_14") (pintype "passive"))
      (node (ref "J3") (pin "16") (pinfunction "16_16") (pintype "passive"))
      (node (ref "J3") (pin "18") (pinfunction "18_18") (pintype "passive"))
      (node (ref "J3") (pin "2") (pinfunction "2_2") (pintype "passive"))
      (node (ref "J3") (pin "20") (pinfunction "20_20") (pintype "passive"))
      (node (ref "J3") (pin "22") (pinfunction "22_22") (pintype "passive"))
      (node (ref "J3") (pin "24") (pinfunction "24_24") (pintype "passive"))
      (node (ref "J3") (pin "4") (pinfunction "4_4") (pintype "passive"))
      (node (ref "J3") (pin "6") (pinfunction "6_6") (pintype "passive"))
      (node (ref "J3") (pin "8") (pinfunction "8_8") (pintype "passive"))
      (node (ref "J4") (pin "10") (pinfunction "10_10") (pintype "passive"))
      (node (ref "J4") (pin "12") (pinfunction "12_12") (pintype "passive"))
      (node (ref "J4") (pin "14") (pinfunction "14_14") (pintype "passive"))
      (node (ref "J4") (pin "16") (pinfunction "16_16") (pintype "passive"))
      (node (ref "J4") (pin "18") (pinfunction "18_18") (pintype "passive"))
      (node (ref "J4") (pin "2") (pinfunction "2_2") (pintype "passive"))
      (node (ref "J4") (pin "20") (pinfunction "20_20") (pintype "passive"))
      (node (ref "J4") (pin "22") (pinfunction "22_22") (pintype "passive"))
      (node (ref "J4") (pin "24") (pinfunction "24_24") (pintype "passive"))
      (node (ref "J4") (pin "4") (pinfunction "4_4") (pintype "passive"))
      (node (ref "J4") (pin "6") (pinfunction "6_6") (pintype "passive"))
      (node (ref "J4") (pin "8") (pinfunction "8_8") (pintype "passive"))
      (node (ref "J5") (pin "10") (pinfunction "10_10") (pintype "passive"))
      (node (ref "J5") (pin "12") (pinfunction "12_12") (pintype "passive"))
      (node (ref "J5") (pin "14") (pinfunction "14_14") (pintype "passive"))
      (node (ref "J5") (pin "16") (pinfunction "16_16") (pintype "passive"))
      (node (ref "J5") (pin "18") (pinfunction "18_18") (pintype "passive"))
      (node (ref "J5") (pin "2") (pinfunction "2_2") (pintype "passive"))
      (node (ref "J5") (pin "20") (pinfunction "20_20") (pintype "passive"))
      (node (ref "J5") (pin "22") (pinfunction "22_22") (pintype "passive"))
      (node (ref "J5") (pin "24") (pinfunction "24_24") (pintype "passive"))
      (node (ref "J5") (pin "4") (pinfunction "4_4") (pintype "passive"))
      (node (ref "J5") (pin "6") (pinfunction "6_6") (pintype "passive"))
      (node (ref "J5") (pin "8") (pinfunction "8_8") (pintype "passive"))
      (node (ref "U1") (pin "12") (pinfunction "GND_12") (pintype "power_in"))
      (node (ref "U1") (pin "15") (pinfunction "~{E}_15") (pintype "input"))
      (node (ref "U2") (pin "12") (pinfunction "GND_12") (pintype "power_in"))
      (node (ref "U2") (pin "15") (pinfunction "~{E}_15") (pintype "input"))
      (node (ref "U3") (pin "12") (pinfunction "GND_12") (pintype "power_in"))
      (node (ref "U3") (pin "15") (pinfunction "~{E}_15") (pintype "input"))
      (node (ref "U4") (pin "12") (pinfunction "GND_12") (pintype "power_in"))
      (node (ref "U4") (pin "15") (pinfunction "~{E}_15") (pintype "input"))
      (node (ref "U5") (pin "12") (pinfunction "GND_12") (pintype "power_in"))
      (node (ref "U5") (pin "15") (pinfunction "~{E}_15") (pintype "input"))
    )
    (net (code "12") (name "Net-(U1-I0)") (class "Default")
      (node (ref "J1") (pin "1") (pinfunction "1_1") (pintype "passive"))
      (node (ref "R1") (pin "2") (pinfunction "2_2") (pintype "passive"))
      (node (ref "U1") (pin "9") (pinfunction "I0_9") (pintype "input"))
    )
    (net (code "13") (name "Net-(U1-I1)") (class "Default")
      (node (ref "J1") (pin "3") (pinfunction "3_3") (pintype "passive"))
      (node (ref "R2") (pin "2") (pinfunction "2_2") (pintype "passive"))
      (node (ref "U1") (pin "8") (pinfunction "I1_8") (pintype "input"))
    )
    (net (code "14") (name "Net-(U1-I2)") (class "Default")
      (node (ref "J1") (pin "5") (pinfunction "5_5") (pintype "passive"))
      (node (ref "R3") (pin "2") (pinfunction "2_2") (pintype "passive"))
      (node (ref "U1") (pin "7") (pinfunction "I2_7") (pintype "input"))
    )
    (net (code "15") (name "Net-(U1-I3)") (class "Default")
      (node (ref "J1") (pin "7") (pinfunction "7_7") (pintype "passive"))
      (node (ref "R4") (pin "2") (pinfunction "2_2") (pintype "passive"))
      (node (ref "U1") (pin "6") (pinfunction "I3_6") (pintype "input"))
    )
    (net (code "16") (name "Net-(U1-I4)") (class "Default")
      (node (ref "J1") (pin "9") (pinfunction "9_9") (pintype "passive"))
      (node (ref "R5") (pin "2") (pinfunction "2_2") (pintype "passive"))
      (node (ref "U1") (pin "5") (pinfunction "I4_5") (pintype "input"))
    )
    (net (code "17") (name "Net-(U1-I5)") (class "Default")
      (node (ref "J1") (pin "11") (pinfunction "11_11") (pintype "passive"))
      (node (ref "R6") (pin "2") (pinfunction "2_2") (pintype "passive"))
      (node (ref "U1") (pin "4") (pinfunction "I5_4") (pintype "input"))
    )
    (net (code "18") (name "Net-(U1-I6)") (class "Default")
      (node (ref "J1") (pin "13") (pinfunction "13_13") (pintype "passive"))
      (node (ref "R7") (pin "2") (pinfunction "2_2") (pintype "passive"))
      (node (ref "U1") (pin "3") (pinfunction "I6_3") (pintype "input"))
    )
    (net (code "19") (name "Net-(U1-I7)") (class "Default")
      (node (ref "J1") (pin "15") (pinfunction "15_15") (pintype "passive"))
      (node (ref "R8") (pin "2") (pinfunction "2_2") (pintype "passive"))
      (node (ref "U1") (pin "2") (pinfunction "I7_2") (pintype "input"))
    )
    (net (code "20") (name "Net-(U1-I8)") (class "Default")
      (node (ref "J1") (pin "17") (pinfunction "17_17") (pintype "passive"))
      (node (ref "R9") (pin "2") (pinfunction "2_2") (pintype "passive"))
      (node (ref "U1") (pin "23") (pinfunction "I8_23") (pintype "input"))
    )
    (net (code "21") (name "Net-(U1-I9)") (class "Default")
      (node (ref "J1") (pin "19") (pinfunction "19_19") (pintype "passive"))
      (node (ref "R10") (pin "2") (pinfunction "2_2") (pintype "passive"))
      (node (ref "U1") (pin "22") (pinfunction "I9_22") (pintype "input"))
    )
    (net (code "22") (name "Net-(U1-I10)") (class "Default")
      (node (ref "J1") (pin "21") (pinfunction "21_21") (pintype "passive"))
      (node (ref "R11") (pin "2") (pinfunction "2_2") (pintype "passive"))
      (node (ref "U1") (pin "21") (pinfunction "I10_21") (pintype "input"))
    )
    (net (code "23") (name "Net-(U1-I11)") (class "Default")
      (node (ref "J1") (pin "23") (pinfunction "23_23") (pintype "passive"))
      (node (ref "R12") (pin "2") (pinfunction "2_2") (pintype "passive"))
      (node (ref "U1") (pin "20") (pinfunction "I11_20") (pintype "input"))
    )
    (net (code "24") (name "Net-(U2-I0)") (class "Default")
      (node (ref "J2") (pin "1") (pinfunction "1_1") (pintype "passive"))
      (node (ref "R13") (pin "2") (pinfunction "2_2") (pintype "passive"))
      (node (ref "U2") (pin "9") (pinfunction "I0_9") (pintype "input"))
    )
    (net (code "25") (name "Net-(U2-I1)") (class "Default")
      (node (ref "J2") (pin "3") (pinfunction "3_3") (pintype "passive"))
      (node (ref "R14") (pin "2") (pinfunction "2_2") (pintype "passive"))
      (node (ref "U2") (pin "8") (pinfunction "I1_8") (pintype "input"))
    )
    (net (code "26") (name "Net-(U2-I2)") (class "Default")
      (node (ref "J2") (pin "5") (pinfunction "5_5") (pintype "passive"))
      (node (ref "R15") (pin "2") (pinfunction "2_2") (pintype "passive"))
      (node (ref "U2") (pin "7") (pinfunction "I2_7") (pintype "input"))
    )
    (net (code "27") (name "Net-(U2-I3)") (class "Default")
      (node (ref "J2") (pin "7") (pinfunction "7_7") (pintype "passive"))
      (node (ref "R16") (pin "2") (pinfunction "2_2") (pintype "passive"))
      (node (ref "U2") (pin "6") (pinfunction "I3_6") (pintype "input"))
    )
    (net (code "28") (name "Net-(U2-I4)") (class "Default")
      (node (ref "J2") (pin "9") (pinfunction "9_9") (pintype "passive"))
      (node (ref "R17") (pin "2") (pinfunction "2_2") (pintype "passive"))
      (node (ref "U2") (pin "5") (pinfunction "I4_5") (pintype "input"))
    )
    (net (code "29") (name "Net-(U2-I5)") (class "Default")
      (node (ref "J2") (pin "11") (pinfunction "11_11") (pintype "passive"))
      (node (ref "R18") (pin "2") (pinfunction "2_2") (pintype "passive"))
      (node (ref "U2") (pin "4") (pinfunction "I5_4") (pintype "input"))
    )
    (net (code "30") (name "Net-(U2-I6)") (class "Default")
      (node (ref "J2") (pin "13") (pinfunction "13_13") (pintype "passive"))
      (node (ref "R19") (pin "2") (pinfunction "2_2") (pintype "passive"))
      (node (ref "U2") (pin "3") (pinfunction "I6_3") (pintype "input"))
    )
    (net (code "31") (name "Net-(U2-I7)") (class "Default")
      (node (ref "J2") (pin "15") (pinfunction "15_15") (pintype "passive"))
      (node (ref "R20") (pin "2") (pinfunction "2_2") (pintype "passive"))
      (node (ref "U2") (pin "2") (pinfunction "I7_2") (pintype "input"))
    )
    (net (code "32") (name "Net-(U2-I8)") (class "Default")
      (node (ref "J2") (pin "17") (pinfunction "17_17") (pintype "passive"))
      (node (ref "R21") (pin "2") (pinfunction "2_2") (pintype "passive"))
      (node (ref "U2") (pin "23") (pinfunction "I8_23") (pintype "input"))
    )
    (net (code "33") (name "Net-(U2-I9)") (class "Default")
      (node (ref "J2") (pin "19") (pinfunction "19_19") (pintype "passive"))
      (node (ref "R22") (pin "2") (pinfunction "2_2") (pintype "passive"))
      (node (ref "U2") (pin "22") (pinfunction "I9_22") (pintype "input"))
    )
    (net (code "34") (name "Net-(U2-I10)") (class "Default")
      (node (ref "J2") (pin "21") (pinfunction "21_21") (pintype "passive"))
      (node (ref "R23") (pin "2") (pinfunction "2_2") (pintype "passive"))
      (node (ref "U2") (pin "21") (pinfunction "I10_21") (pintype "input"))
    )
    (net (code "35") (name "Net-(U2-I11)") (class "Default")
      (node (ref "J2") (pin "23") (pinfunction "23_23") (pintype "passive"))
      (node (ref "R24") (pin "2") (pinfunction "2_2") (pintype "passive"))
      (node (ref "U2") (pin "20") (pinfunction "I11_20") (pintype "input"))
    )
    (net (code "36") (name "Net-(U3-I0)") (class "Default")
      (node (ref "J3") (pin "1") (pinfunction "1_1") (pintype "passive"))
      (node (ref "R25") (pin "2") (pinfunction "2_2") (pintype "passive"))
      (node (ref "U3") (pin "9") (pinfunction "I0_9") (pintype "input"))
    )
    (net (code "37") (name "Net-(U3-I1)") (class "Default")
      (node (ref "J3") (pin "3") (pinfunction "3_3") (pintype "passive"))
      (node (ref "R26") (pin "2") (pinfunction "2_2") (pintype "passive"))
      (node (ref "U3") (pin "8") (pinfunction "I1_8") (pintype "input"))
    )
    (net (code "38") (name "Net-(U3-I2)") (class "Default")
      (node (ref "J3") (pin "5") (pinfunction "5_5") (pintype "passive"))
      (node (ref "R27") (pin "2") (pinfunction "2_2") (pintype "passive"))
      (node (ref "U3") (pin "7") (pinfunction "I2_7") (pintype "input"))
    )
    (net (code "39") (name "Net-(U3-I3)") (class "Default")
      (node (ref "J3") (pin "7") (pinfunction "7_7") (pintype "passive"))
      (node (ref "R28") (pin "2") (pinfunction "2_2") (pintype "passive"))
      (node (ref "U3") (pin "6") (pinfunction "I3_6") (pintype "input"))
    )
    (net (code "40") (name "Net-(U3-I4)") (class "Default")
      (node (ref "J3") (pin "9") (pinfunction "9_9") (pintype "passive"))
      (node (ref "R29") (pin "2") (pinfunction "2_2") (pintype "passive"))
      (node (ref "U3") (pin "5") (pinfunction "I4_5") (pintype "input"))
    )
    (net (code "41") (name "Net-(U3-I5)") (class "Default")
      (node (ref "J3") (pin "11") (pinfunction "11_11") (pintype "passive"))
      (node (ref "R30") (pin "2") (pinfunction "2_2") (pintype "passive"))
      (node (ref "U3") (pin "4") (pinfunction "I5_4") (pintype "input"))
    )
    (net (code "42") (name "Net-(U3-I6)") (class "Default")
      (node (ref "J3") (pin "13") (pinfunction "13_13") (pintype "passive"))
      (node (ref "R31") (pin "2") (pinfunction "2_2") (pintype "passive"))
      (node (ref "U3") (pin "3") (pinfunction "I6_3") (pintype "input"))
    )
    (net (code "43") (name "Net-(U3-I7)") (class "Default")
      (node (ref "J3") (pin "15") (pinfunction "15_15") (pintype "passive"))
      (node (ref "R32") (pin "2") (pinfunction "2_2") (pintype "passive"))
      (node (ref "U3") (pin "2") (pinfunction "I7_2") (pintype "input"))
    )
    (net (code "44") (name "Net-(U3-I8)") (class "Default")
      (node (ref "J3") (pin "17") (pinfunction "17_17") (pintype "passive"))
      (node (ref "R33") (pin "2") (pinfunction "2_2") (pintype "passive"))
      (node (ref "U3") (pin "23") (pinfunction "I8_23") (pintype "input"))
    )
    (net (code "45") (name "Net-(U3-I9)") (class "Default")
      (node (ref "J3") (pin "19") (pinfunction "19_19") (pintype "passive"))
      (node (ref "R34") (pin "2") (pinfunction "2_2") (pintype "passive"))
      (node (ref "U3") (pin "22") (pinfunction "I9_22") (pintype "input"))
    )
    (net (code "46") (name "Net-(U3-I10)") (class "Default")
      (node (ref "J3") (pin "21") (pinfunction "21_21") (pintype "passive"))
      (node (ref "R35") (pin "2") (pinfunction "2_2") (pintype "passive"))
      (node (ref "U3") (pin "21") (pinfunction "I10_21") (pintype "input"))
    )
    (net (code "47") (name "Net-(U3-I11)") (class "Default")
      (node (ref "J3") (pin "23") (pinfunction "23_23") (pintype "passive"))
      (node (ref "R36") (pin "2") (pinfunction "2_2") (pintype "passive"))
      (node (ref "U3") (pin "20") (pinfunction "I11_20") (pintype "input"))
    )
    (net (code "48") (name "Net-(U4-I0)") (class "Default")
      (node (ref "J4") (pin "1") (pinfunction "1_1") (pintype "passive"))
      (node (ref "R37") (pin "2") (pinfunction "2_2") (pintype "passive"))
      (node (ref "U4") (pin "9") (pinfunction "I0_9") (pintype "input"))
    )
    (net (code "49") (name "Net-(U4-I1)") (class "Default")
      (node (ref "J4") (pin "3") (pinfunction "3_3") (pintype "passive"))
      (node (ref "R38") (pin "2") (pinfunction "2_2") (pintype "passive"))
      (node (ref "U4") (pin "8") (pinfunction "I1_8") (pintype "input"))
    )
    (net (code "50") (name "Net-(U4-I2)") (class "Default")
      (node (ref "J4") (pin "5") (pinfunction "5_5") (pintype "passive"))
      (node (ref "R39") (pin "2") (pinfunction "2_2") (pintype "passive"))
      (node (ref "U4") (pin "7") (pinfunction "I2_7") (pintype "input"))
    )
    (net (code "51") (name "Net-(U4-I3)") (class "Default")
      (node (ref "J4") (pin "7") (pinfunction "7_7") (pintype "passive"))
      (node (ref "R40") (pin "2") (pinfunction "2_2") (pintype "passive"))
      (node (ref "U4") (pin "6") (pinfunction "I3_6") (pintype "input"))
    )
    (net (code "52") (name "Net-(U4-I4)") (class "Default")
      (node (ref "J4") (pin "9") (pinfunction "9_9") (pintype "passive"))
      (node (ref "R41") (pin "2") (pinfunction "2_2") (pintype "passive"))
      (node (ref "U4") (pin "5") (pinfunction "I4_5") (pintype "input"))
    )
    (net (code "53") (name "Net-(U4-I5)") (class "Default")
      (node (ref "J4") (pin "11") (pinfunction "11_11") (pintype "passive"))
      (node (ref "R42") (pin "2") (pinfunction "2_2") (pintype "passive"))
      (node (ref "U4") (pin "4") (pinfunction "I5_4") (pintype "input"))
    )
    (net (code "54") (name "Net-(U4-I6)") (class "Default")
      (node (ref "J4") (pin "13") (pinfunction "13_13") (pintype "passive"))
      (node (ref "R43") (pin "2") (pinfunction "2_2") (pintype "passive"))
      (node (ref "U4") (pin "3") (pinfunction "I6_3") (pintype "input"))
    )
    (net (code "55") (name "Net-(U4-I7)") (class "Default")
      (node (ref "J4") (pin "15") (pinfunction "15_15") (pintype "passive"))
      (node (ref "R44") (pin "2") (pinfunction "2_2") (pintype "passive"))
      (node (ref "U4") (pin "2") (pinfunction "I7_2") (pintype "input"))
    )
    (net (code "56") (name "Net-(U4-I8)") (class "Default")
      (node (ref "J4") (pin "17") (pinfunction "17_17") (pintype "passive"))
      (node (ref "R45") (pin "2") (pinfunction "2_2") (pintype "passive"))
      (node (ref "U4") (pin "23") (pinfunction "I8_23") (pintype "input"))
    )
    (net (code "57") (name "Net-(U4-I9)") (class "Default")
      (node (ref "J4") (pin "19") (pinfunction "19_19") (pintype "passive"))
      (node (ref "R46") (pin "2") (pinfunction "2_2") (pintype "passive"))
      (node (ref "U4") (pin "22") (pinfunction "I9_22") (pintype "input"))
    )
    (net (code "58") (name "Net-(U4-I10)") (class "Default")
      (node (ref "J4") (pin "21") (pinfunction "21_21") (pintype "passive"))
      (node (ref "R47") (pin "2") (pinfunction "2_2") (pintype "passive"))
      (node (ref "U4") (pin "21") (pinfunction "I10_21") (pintype "input"))
    )
    (net (code "59") (name "Net-(U4-I11)") (class "Default")
      (node (ref "J4") (pin "23") (pinfunction "23_23") (pintype "passive"))
      (node (ref "R48") (pin "2") (pinfunction "2_2") (pintype "passive"))
      (node (ref "U4") (pin "20") (pinfunction "I11_20") (pintype "input"))
    )
    (net (code "60") (name "Net-(U5-I0)") (class "Default")
      (node (ref "J5") (pin "1") (pinfunction "1_1") (pintype "passive"))
      (node (ref "R49") (pin "2") (pinfunction "2_2") (pintype "passive"))
      (node (ref "U5") (pin "9") (pinfunction "I0_9") (pintype "input"))
    )
    (net (code "61") (name "Net-(U5-I1)") (class "Default")
      (node (ref "J5") (pin "3") (pinfunction "3_3") (pintype "passive"))
      (node (ref "R50") (pin "2") (pinfunction "2_2") (pintype "passive"))
      (node (ref "U5") (pin "8") (pinfunction "I1_8") (pintype "input"))
    )
    (net (code "62") (name "Net-(U5-I2)") (class "Default")
      (node (ref "J5") (pin "5") (pinfunction "5_5") (pintype "passive"))
      (node (ref "R51") (pin "2") (pinfunction "2_2") (pintype "passive"))
      (node (ref "U5") (pin "7") (pinfunction "I2_7") (pintype "input"))
    )
    (net (code "63") (name "Net-(U5-I3)") (class "Default")
      (node (ref "J5") (pin "7") (pinfunction "7_7") (pintype "passive"))
      (node (ref "R52") (pin "2") (pinfunction "2_2") (pintype "passive"))
      (node (ref "U5") (pin "6") (pinfunction "I3_6") (pintype "input"))
    )
    (net (code "64") (name "Net-(U5-I4)") (class "Default")
      (node (ref "J5") (pin "9") (pinfunction "9_9") (pintype "passive"))
      (node (ref "R53") (pin "2") (pinfunction "2_2") (pintype "passive"))
      (node (ref "U5") (pin "5") (pinfunction "I4_5") (pintype "input"))
    )
    (net (code "65") (name "Net-(U5-I5)") (class "Default")
      (node (ref "J5") (pin "11") (pinfunction "11_11") (pintype "passive"))
      (node (ref "R54") (pin "2") (pinfunction "2_2") (pintype "passive"))
      (node (ref "U5") (pin "4") (pinfunction "I5_4") (pintype "input"))
    )
    (net (code "66") (name "Net-(U5-I6)") (class "Default")
      (node (ref "J5") (pin "13") (pinfunction "13_13") (pintype "passive"))
      (node (ref "R55") (pin "2") (pinfunction "2_2") (pintype "passive"))
      (node (ref "U5") (pin "3") (pinfunction "I6_3") (pintype "input"))
    )
    (net (code "67") (name "Net-(U5-I7)") (class "Default")
      (node (ref "J5") (pin "15") (pinfunction "15_15") (pintype "passive"))
      (node (ref "R56") (pin "2") (pinfunction "2_2") (pintype "passive"))
      (node (ref "U5") (pin "2") (pinfunction "I7_2") (pintype "input"))
    )
    (net (code "68") (name "Net-(U5-I8)") (class "Default")
      (node (ref "J5") (pin "17") (pinfunction "17_17") (pintype "passive"))
      (node (ref "R57") (pin "2") (pinfunction "2_2") (pintype "passive"))
      (node (ref "U5") (pin "23") (pinfunction "I8_23") (pintype "input"))
    )
    (net (code "69") (name "Net-(U5-I9)") (class "Default")
      (node (ref "J5") (pin "19") (pinfunction "19_19") (pintype "passive"))
      (node (ref "R58") (pin "2") (pinfunction "2_2") (pintype "passive"))
      (node (ref "U5") (pin "22") (pinfunction "I9_22") (pintype "input"))
    )
    (net (code "70") (name "Net-(U5-I10)") (class "Default")
      (node (ref "J5") (pin "21") (pinfunction "21_21") (pintype "passive"))
      (node (ref "R59") (pin "2") (pinfunction "2_2") (pintype "passive"))
      (node (ref "U5") (pin "21") (pinfunction "I10_21") (pintype "input"))
    )
    (net (code "71") (name "Net-(U5-I11)") (class "Default")
      (node (ref "J5") (pin "23") (pinfunction "23_23") (pintype "passive"))
      (node (ref "R60") (pin "2") (pinfunction "2_2") (pintype "passive"))
      (node (ref "U5") (pin "20") (pinfunction "I11_20") (pintype "input"))
    )
    (net (code "72") (name "unconnected-(U1-I12-Pad19)") (class "Default")
      (node (ref "U1") (pin "19") (pinfunction "I12_19") (pintype "input+no_connect"))
    )
    (net (code "73") (name "unconnected-(U1-I13-Pad18)") (class "Default")
      (node (ref "U1") (pin "18") (pinfunction "I13_18") (pintype "input+no_connect"))
    )
    (net (code "74") (name "unconnected-(U1-I14-Pad17)") (class "Default")
      (node (ref "U1") (pin "17") (pinfunction "I14_17") (pintype "input+no_connect"))
    )
    (net (code "75") (name "unconnected-(U1-I15-Pad16)") (class "Default")
      (node (ref "U1") (pin "16") (pinfunction "I15_16") (pintype "input+no_connect"))
    )
    (net (code "76") (name "unconnected-(U2-I12-Pad19)") (class "Default")
      (node (ref "U2") (pin "19") (pinfunction "I12_19") (pintype "input+no_connect"))
    )
    (net (code "77") (name "unconnected-(U2-I13-Pad18)") (class "Default")
      (node (ref "U2") (pin "18") (pinfunction "I13_18") (pintype "input+no_connect"))
    )
    (net (code "78") (name "unconnected-(U2-I14-Pad17)") (class "Default")
      (node (ref "U2") (pin "17") (pinfunction "I14_17") (pintype "input+no_connect"))
    )
    (net (code "79") (name "unconnected-(U2-I15-Pad16)") (class "Default")
      (node (ref "U2") (pin "16") (pinfunction "I15_16") (pintype "input+no_connect"))
    )
    (net (code "80") (name "unconnected-(U3-I12-Pad19)") (class "Default")
      (node (ref "U3") (pin "19") (pinfunction "I12_19") (pintype "input+no_connect"))
    )
    (net (code "81") (name "unconnected-(U3-I13-Pad18)") (class "Default")
      (node (ref "U3") (pin "18") (pinfunction "I13_18") (pintype "input+no_connect"))
    )
    (net (code "82") (name "unconnected-(U3-I14-Pad17)") (class "Default")
      (node (ref "U3") (pin "17") (pinfunction "I14_17") (pintype "input+no_connect"))
    )
    (net (code "83") (name "unconnected-(U3-I15-Pad16)") (class "Default")
      (node (ref "U3") (pin "16") (pinfunction "I15_16") (pintype "input+no_connect"))
    )
    (net (code "84") (name "unconnected-(U4-I12-Pad19)") (class "Default")
      (node (ref "U4") (pin "19") (pinfunction "I12_19") (pintype "input+no_connect"))
    )
    (net (code "85") (name "unconnected-(U4-I13-Pad18)") (class "Default")
      (node (ref "U4") (pin "18") (pinfunction "I13_18") (pintype "input+no_connect"))
    )
    (net (code "86") (name "unconnected-(U4-I14-Pad17)") (class "Default")
      (node (ref "U4") (pin "17") (pinfunction "I14_17") (pintype "input+no_connect"))
    )
    (net (code "87") (name "unconnected-(U4-I15-Pad16)") (class "Default")
      (node (ref "U4") (pin "16") (pinfunction "I15_16") (pintype "input+no_connect"))
    )
    (net (code "88") (name "unconnected-(U5-I12-Pad19)") (class "Default")
      (node (ref "U5") (pin "19") (pinfunction "I12_19") (pintype "input+no_connect"))
    )
    (net (code "89") (name "unconnected-(U5-I13-Pad18)") (class "Default")
      (node (ref "U5") (pin "18") (pinfunction "I13_18") (pintype "input+no_connect"))
    )
    (net (code "90") (name "unconnected-(U5-I14-Pad17)") (class "Default")
      (node (ref "U5") (pin "17") (pinfunction "I14_17") (pintype "input+no_connect"))
    )
    (net (code "91") (name "unconnected-(U5-I15-Pad16)") (class "Default")
      (node (ref "U5") (pin "16") (pinfunction "I15_16") (pintype "input+no_connect"))
    )
  )
)
